# ADC_Test.net
KiCad netlist of a schematic drawn in EAGLE
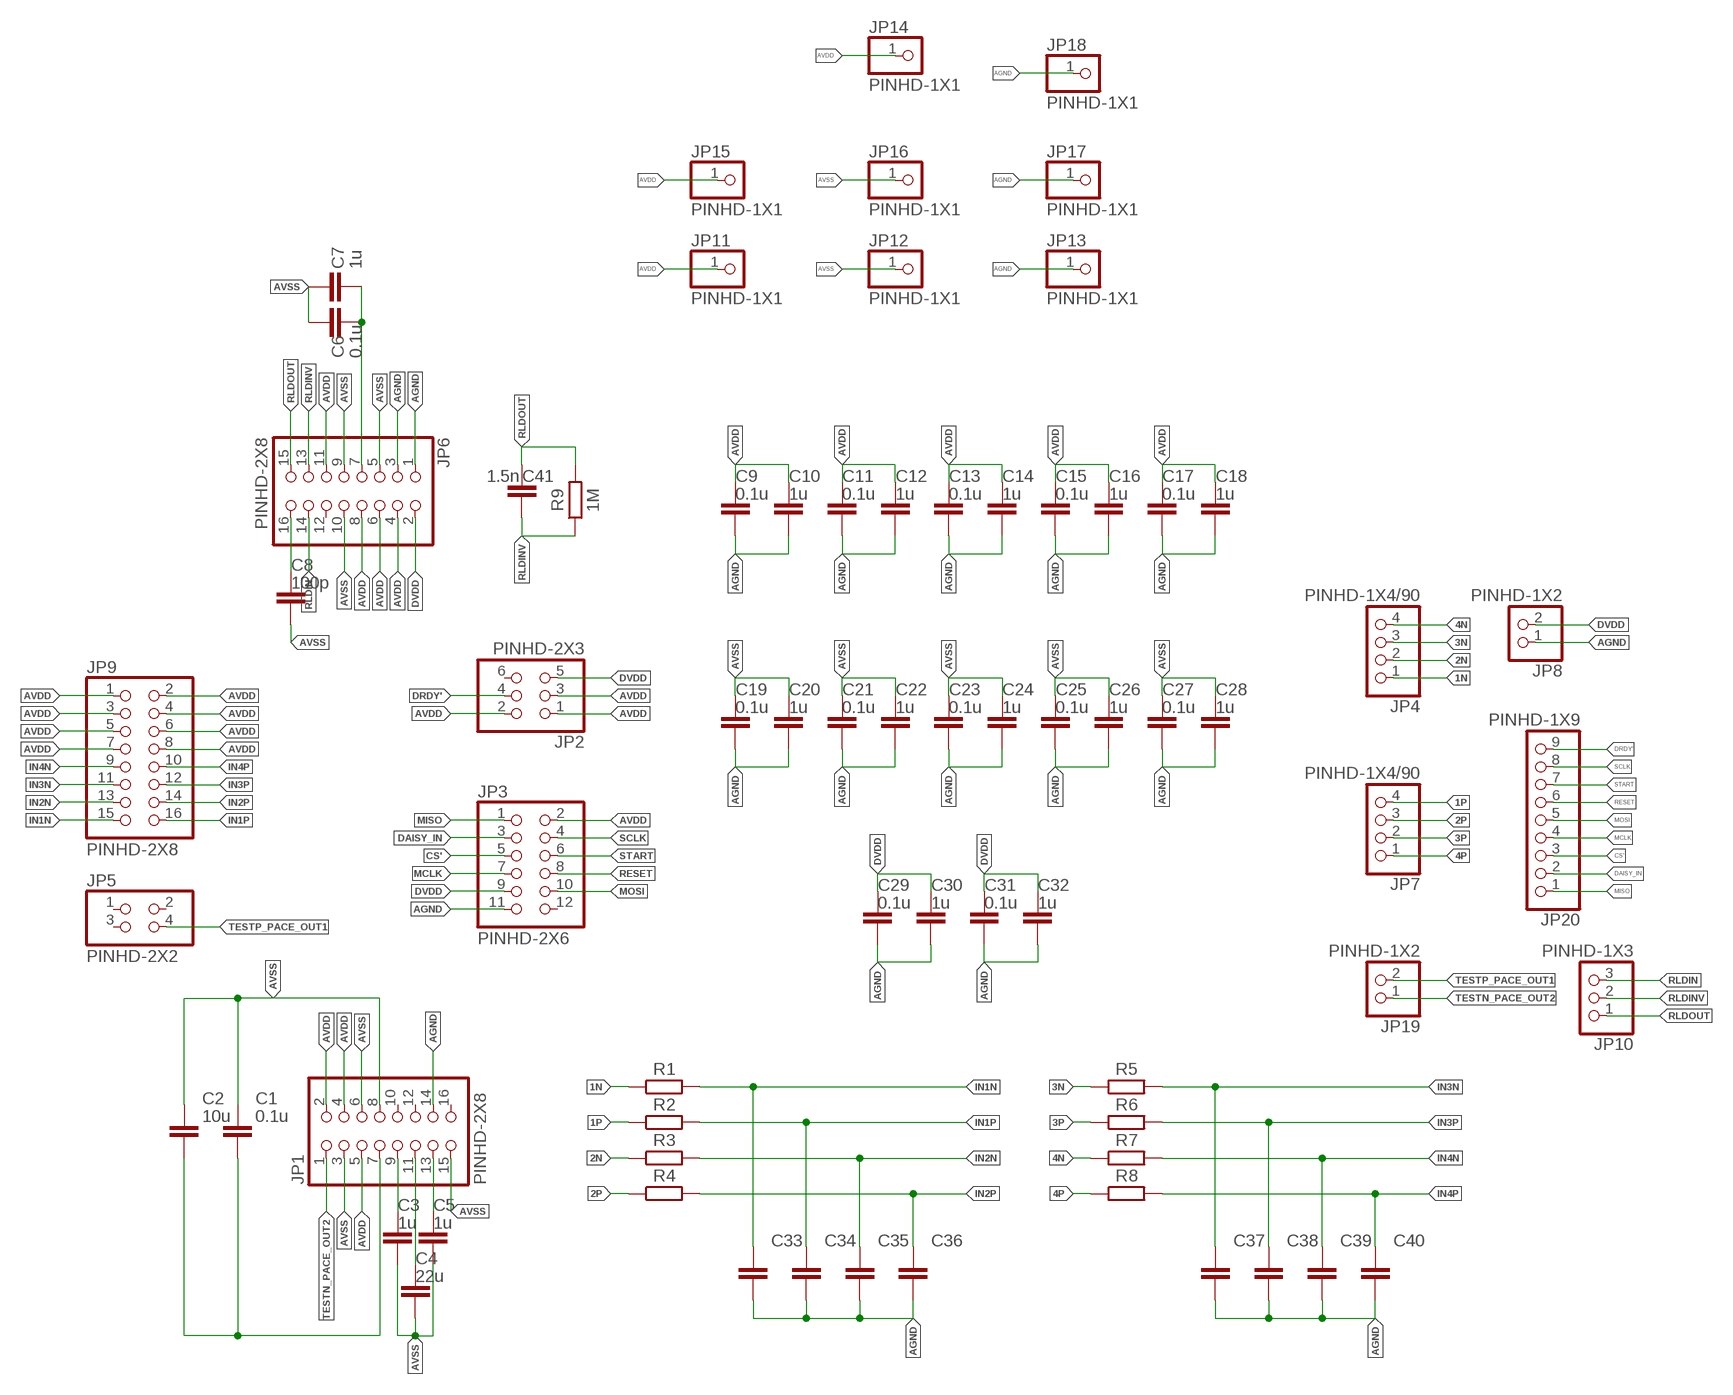
[diagram p0: schematic, sheet 1]

(export (version "E")
  (design (tool "Eeschema 10.0.6"))
  (components
    (comp (ref "C1")
      (value "0.1u")
      (footprint "eagle-import:CAPC2012X110")
      (libsource (lib "eagle-import") (part "CCHIP-0805(2012-METRIC)_"))
    )
    (comp (ref "C2")
      (value "10u")
      (footprint "eagle-import:CAPC2012X110")
      (libsource (lib "eagle-import") (part "CCHIP-0805(2012-METRIC)_"))
    )
    (comp (ref "C3")
      (value "1u")
      (footprint "eagle-import:CAPC2012X110")
      (libsource (lib "eagle-import") (part "CCHIP-0805(2012-METRIC)_"))
    )
    (comp (ref "C4")
      (value "22u")
      (footprint "eagle-import:CAPC2012X110")
      (libsource (lib "eagle-import") (part "CCHIP-0805(2012-METRIC)_"))
    )
    (comp (ref "C5")
      (value "1u")
      (footprint "eagle-import:CAPC2012X110")
      (libsource (lib "eagle-import") (part "CCHIP-0805(2012-METRIC)_"))
    )
    (comp (ref "C6")
      (value "0.1u")
      (footprint "eagle-import:CAPC2012X110")
      (libsource (lib "eagle-import") (part "CCHIP-0805(2012-METRIC)_"))
    )
    (comp (ref "C7")
      (value "1u")
      (footprint "eagle-import:CAPC2012X110")
      (libsource (lib "eagle-import") (part "CCHIP-0805(2012-METRIC)_"))
    )
    (comp (ref "C8")
      (value "100p")
      (footprint "eagle-import:CAPC2012X110")
      (libsource (lib "eagle-import") (part "CCHIP-0805(2012-METRIC)_"))
    )
    (comp (ref "C9")
      (value "0.1u")
      (footprint "eagle-import:CAPC2012X110")
      (libsource (lib "eagle-import") (part "CCHIP-0805(2012-METRIC)_"))
    )
    (comp (ref "C10")
      (value "1u")
      (footprint "eagle-import:CAPC2012X110")
      (libsource (lib "eagle-import") (part "CCHIP-0805(2012-METRIC)_"))
    )
    (comp (ref "C11")
      (value "0.1u")
      (footprint "eagle-import:CAPC2012X110")
      (libsource (lib "eagle-import") (part "CCHIP-0805(2012-METRIC)_"))
    )
    (comp (ref "C12")
      (value "1u")
      (footprint "eagle-import:CAPC2012X110")
      (libsource (lib "eagle-import") (part "CCHIP-0805(2012-METRIC)_"))
    )
    (comp (ref "C13")
      (value "0.1u")
      (footprint "eagle-import:CAPC2012X110")
      (libsource (lib "eagle-import") (part "CCHIP-0805(2012-METRIC)_"))
    )
    (comp (ref "C14")
      (value "1u")
      (footprint "eagle-import:CAPC2012X110")
      (libsource (lib "eagle-import") (part "CCHIP-0805(2012-METRIC)_"))
    )
    (comp (ref "C15")
      (value "0.1u")
      (footprint "eagle-import:CAPC2012X110")
      (libsource (lib "eagle-import") (part "CCHIP-0805(2012-METRIC)_"))
    )
    (comp (ref "C16")
      (value "1u")
      (footprint "eagle-import:CAPC2012X110")
      (libsource (lib "eagle-import") (part "CCHIP-0805(2012-METRIC)_"))
    )
    (comp (ref "C17")
      (value "0.1u")
      (footprint "eagle-import:CAPC2012X110")
      (libsource (lib "eagle-import") (part "CCHIP-0805(2012-METRIC)_"))
    )
    (comp (ref "C18")
      (value "1u")
      (footprint "eagle-import:CAPC2012X110")
      (libsource (lib "eagle-import") (part "CCHIP-0805(2012-METRIC)_"))
    )
    (comp (ref "C19")
      (value "0.1u")
      (footprint "eagle-import:CAPC2012X110")
      (libsource (lib "eagle-import") (part "CCHIP-0805(2012-METRIC)_"))
    )
    (comp (ref "C20")
      (value "1u")
      (footprint "eagle-import:CAPC2012X110")
      (libsource (lib "eagle-import") (part "CCHIP-0805(2012-METRIC)_"))
    )
    (comp (ref "C21")
      (value "0.1u")
      (footprint "eagle-import:CAPC2012X110")
      (libsource (lib "eagle-import") (part "CCHIP-0805(2012-METRIC)_"))
    )
    (comp (ref "C22")
      (value "1u")
      (footprint "eagle-import:CAPC2012X110")
      (libsource (lib "eagle-import") (part "CCHIP-0805(2012-METRIC)_"))
    )
    (comp (ref "C23")
      (value "0.1u")
      (footprint "eagle-import:CAPC2012X110")
      (libsource (lib "eagle-import") (part "CCHIP-0805(2012-METRIC)_"))
    )
    (comp (ref "C24")
      (value "1u")
      (footprint "eagle-import:CAPC2012X110")
      (libsource (lib "eagle-import") (part "CCHIP-0805(2012-METRIC)_"))
    )
    (comp (ref "C25")
      (value "0.1u")
      (footprint "eagle-import:CAPC2012X110")
      (libsource (lib "eagle-import") (part "CCHIP-0805(2012-METRIC)_"))
    )
    (comp (ref "C26")
      (value "1u")
      (footprint "eagle-import:CAPC2012X110")
      (libsource (lib "eagle-import") (part "CCHIP-0805(2012-METRIC)_"))
    )
    (comp (ref "C27")
      (value "0.1u")
      (footprint "eagle-import:CAPC2012X110")
      (libsource (lib "eagle-import") (part "CCHIP-0805(2012-METRIC)_"))
    )
    (comp (ref "C28")
      (value "1u")
      (footprint "eagle-import:CAPC2012X110")
      (libsource (lib "eagle-import") (part "CCHIP-0805(2012-METRIC)_"))
    )
    (comp (ref "C29")
      (value "0.1u")
      (footprint "eagle-import:CAPC2012X110")
      (libsource (lib "eagle-import") (part "CCHIP-0805(2012-METRIC)_"))
    )
    (comp (ref "C30")
      (value "1u")
      (footprint "eagle-import:CAPC2012X110")
      (libsource (lib "eagle-import") (part "CCHIP-0805(2012-METRIC)_"))
    )
    (comp (ref "C31")
      (value "0.1u")
      (footprint "eagle-import:CAPC2012X110")
      (libsource (lib "eagle-import") (part "CCHIP-0805(2012-METRIC)_"))
    )
    (comp (ref "C32")
      (value "1u")
      (footprint "eagle-import:CAPC2012X110")
      (libsource (lib "eagle-import") (part "CCHIP-0805(2012-METRIC)_"))
    )
    (comp (ref "C33")
      (value "C_CHIP-0805(2012-METRIC)")
      (footprint "eagle-import:CAPC2012X110")
      (libsource (lib "eagle-import") (part "CCHIP-0805(2012-METRIC)_"))
    )
    (comp (ref "C34")
      (value "C_CHIP-0805(2012-METRIC)")
      (footprint "eagle-import:CAPC2012X110")
      (libsource (lib "eagle-import") (part "CCHIP-0805(2012-METRIC)_"))
    )
    (comp (ref "C35")
      (value "C_CHIP-0805(2012-METRIC)")
      (footprint "eagle-import:CAPC2012X110")
      (libsource (lib "eagle-import") (part "CCHIP-0805(2012-METRIC)_"))
    )
    (comp (ref "C36")
      (value "C_CHIP-0805(2012-METRIC)")
      (footprint "eagle-import:CAPC2012X110")
      (libsource (lib "eagle-import") (part "CCHIP-0805(2012-METRIC)_"))
    )
    (comp (ref "C37")
      (value "C_CHIP-0805(2012-METRIC)")
      (footprint "eagle-import:CAPC2012X110")
      (libsource (lib "eagle-import") (part "CCHIP-0805(2012-METRIC)_"))
    )
    (comp (ref "C38")
      (value "C_CHIP-0805(2012-METRIC)")
      (footprint "eagle-import:CAPC2012X110")
      (libsource (lib "eagle-import") (part "CCHIP-0805(2012-METRIC)_"))
    )
    (comp (ref "C39")
      (value "C_CHIP-0805(2012-METRIC)")
      (footprint "eagle-import:CAPC2012X110")
      (libsource (lib "eagle-import") (part "CCHIP-0805(2012-METRIC)_"))
    )
    (comp (ref "C40")
      (value "C_CHIP-0805(2012-METRIC)")
      (footprint "eagle-import:CAPC2012X110")
      (libsource (lib "eagle-import") (part "CCHIP-0805(2012-METRIC)_"))
    )
    (comp (ref "C41")
      (value "1.5n")
      (footprint "eagle-import:CAPC2012X110")
      (libsource (lib "eagle-import") (part "CCHIP-0805(2012-METRIC)_"))
    )
    (comp (ref "JP1")
      (value "PINHD-2X8")
      (footprint "eagle-import:2X08")
      (libsource (lib "eagle-import") (part "PINHD-2X8"))
    )
    (comp (ref "JP2")
      (value "PINHD-2X3")
      (footprint "eagle-import:2X03")
      (libsource (lib "eagle-import") (part "PINHD-2X3"))
    )
    (comp (ref "JP3")
      (value "PINHD-2X6")
      (footprint "eagle-import:2X06")
      (libsource (lib "eagle-import") (part "PINHD-2X6"))
    )
    (comp (ref "JP4")
      (value "PINHD-1X4/90")
      (footprint "eagle-import:1X04_90")
      (libsource (lib "eagle-import") (part "PINHD-1X4/90"))
    )
    (comp (ref "JP5")
      (value "PINHD-2X2")
      (footprint "eagle-import:2X02")
      (libsource (lib "eagle-import") (part "PINHD-2X2"))
    )
    (comp (ref "JP6")
      (value "PINHD-2X8")
      (footprint "eagle-import:2X08")
      (libsource (lib "eagle-import") (part "PINHD-2X8"))
    )
    (comp (ref "JP7")
      (value "PINHD-1X4/90")
      (footprint "eagle-import:1X04_90")
      (libsource (lib "eagle-import") (part "PINHD-1X4/90"))
    )
    (comp (ref "JP8")
      (value "PINHD-1X2")
      (footprint "eagle-import:1X02")
      (libsource (lib "eagle-import") (part "PINHD-1X2"))
    )
    (comp (ref "JP9")
      (value "PINHD-2X8")
      (footprint "eagle-import:2X08")
      (libsource (lib "eagle-import") (part "PINHD-2X8"))
    )
    (comp (ref "JP10")
      (value "PINHD-1X3")
      (footprint "eagle-import:1X03")
      (libsource (lib "eagle-import") (part "PINHD-1X3"))
    )
    (comp (ref "JP11")
      (value "PINHD-1X1")
      (footprint "eagle-import:1X01")
      (libsource (lib "eagle-import") (part "PINHD-1X1"))
    )
    (comp (ref "JP12")
      (value "PINHD-1X1")
      (footprint "eagle-import:1X01")
      (libsource (lib "eagle-import") (part "PINHD-1X1"))
    )
    (comp (ref "JP13")
      (value "PINHD-1X1")
      (footprint "eagle-import:1X01")
      (libsource (lib "eagle-import") (part "PINHD-1X1"))
    )
    (comp (ref "JP14")
      (value "PINHD-1X1")
      (footprint "eagle-import:1X01")
      (libsource (lib "eagle-import") (part "PINHD-1X1"))
    )
    (comp (ref "JP15")
      (value "PINHD-1X1")
      (footprint "eagle-import:1X01")
      (libsource (lib "eagle-import") (part "PINHD-1X1"))
    )
    (comp (ref "JP16")
      (value "PINHD-1X1")
      (footprint "eagle-import:1X01")
      (libsource (lib "eagle-import") (part "PINHD-1X1"))
    )
    (comp (ref "JP17")
      (value "PINHD-1X1")
      (footprint "eagle-import:1X01")
      (libsource (lib "eagle-import") (part "PINHD-1X1"))
    )
    (comp (ref "JP18")
      (value "PINHD-1X1")
      (footprint "eagle-import:1X01")
      (libsource (lib "eagle-import") (part "PINHD-1X1"))
    )
    (comp (ref "JP19")
      (value "PINHD-1X2")
      (footprint "eagle-import:1X02")
      (libsource (lib "eagle-import") (part "PINHD-1X2"))
    )
    (comp (ref "JP20")
      (value "PINHD-1X9")
      (footprint "eagle-import:1X09")
      (libsource (lib "eagle-import") (part "PINHD-1X9"))
    )
    (comp (ref "R1")
      (value "R_CHIP-1206(3216-METRIC)")
      (footprint "eagle-import:RESC3216X70")
      (libsource (lib "eagle-import") (part "RCHIP-1206(3216-METRIC)_"))
    )
    (comp (ref "R2")
      (value "R_CHIP-1206(3216-METRIC)")
      (footprint "eagle-import:RESC3216X70")
      (libsource (lib "eagle-import") (part "RCHIP-1206(3216-METRIC)_"))
    )
    (comp (ref "R3")
      (value "R_CHIP-1206(3216-METRIC)")
      (footprint "eagle-import:RESC3216X70")
      (libsource (lib "eagle-import") (part "RCHIP-1206(3216-METRIC)_"))
    )
    (comp (ref "R4")
      (value "R_CHIP-1206(3216-METRIC)")
      (footprint "eagle-import:RESC3216X70")
      (libsource (lib "eagle-import") (part "RCHIP-1206(3216-METRIC)_"))
    )
    (comp (ref "R5")
      (value "R_CHIP-1206(3216-METRIC)")
      (footprint "eagle-import:RESC3216X70")
      (libsource (lib "eagle-import") (part "RCHIP-1206(3216-METRIC)_"))
    )
    (comp (ref "R6")
      (value "R_CHIP-1206(3216-METRIC)")
      (footprint "eagle-import:RESC3216X70")
      (libsource (lib "eagle-import") (part "RCHIP-1206(3216-METRIC)_"))
    )
    (comp (ref "R7")
      (value "R_CHIP-1206(3216-METRIC)")
      (footprint "eagle-import:RESC3216X70")
      (libsource (lib "eagle-import") (part "RCHIP-1206(3216-METRIC)_"))
    )
    (comp (ref "R8")
      (value "R_CHIP-1206(3216-METRIC)")
      (footprint "eagle-import:RESC3216X70")
      (libsource (lib "eagle-import") (part "RCHIP-1206(3216-METRIC)_"))
    )
    (comp (ref "R9")
      (value "1M")
      (footprint "eagle-import:RESC3216X70")
      (libsource (lib "eagle-import") (part "RCHIP-1206(3216-METRIC)_"))
    )
  )
  (nets
    (net (code "1") (name "1N") (class "Default")
      (node (ref "JP4") (pin "1") (pinfunction "1_1") (pintype "passive"))
      (node (ref "R1") (pin "1") (pinfunction "1_1") (pintype "passive"))
    )
    (net (code "2") (name "1P") (class "Default")
      (node (ref "JP7") (pin "4") (pinfunction "4_4") (pintype "passive"))
      (node (ref "R2") (pin "1") (pinfunction "1_1") (pintype "passive"))
    )
    (net (code "3") (name "2N") (class "Default")
      (node (ref "JP4") (pin "2") (pinfunction "2_2") (pintype "passive"))
      (node (ref "R3") (pin "1") (pinfunction "1_1") (pintype "passive"))
    )
    (net (code "4") (name "2P") (class "Default")
      (node (ref "JP7") (pin "3") (pinfunction "3_3") (pintype "passive"))
      (node (ref "R4") (pin "1") (pinfunction "1_1") (pintype "passive"))
    )
    (net (code "5") (name "3N") (class "Default")
      (node (ref "JP4") (pin "3") (pinfunction "3_3") (pintype "passive"))
      (node (ref "R5") (pin "1") (pinfunction "1_1") (pintype "passive"))
    )
    (net (code "6") (name "3P") (class "Default")
      (node (ref "JP7") (pin "2") (pinfunction "2_2") (pintype "passive"))
      (node (ref "R6") (pin "1") (pinfunction "1_1") (pintype "passive"))
    )
    (net (code "7") (name "4N") (class "Default")
      (node (ref "JP4") (pin "4") (pinfunction "4_4") (pintype "passive"))
      (node (ref "R7") (pin "1") (pinfunction "1_1") (pintype "passive"))
    )
    (net (code "8") (name "4P") (class "Default")
      (node (ref "JP7") (pin "1") (pinfunction "1_1") (pintype "passive"))
      (node (ref "R8") (pin "1") (pinfunction "1_1") (pintype "passive"))
    )
    (net (code "9") (name "AGND") (class "Default")
      (node (ref "C10") (pin "2") (pinfunction "2_2") (pintype "passive"))
      (node (ref "C11") (pin "2") (pinfunction "2_2") (pintype "passive"))
      (node (ref "C12") (pin "2") (pinfunction "2_2") (pintype "passive"))
      (node (ref "C13") (pin "2") (pinfunction "2_2") (pintype "passive"))
      (node (ref "C14") (pin "2") (pinfunction "2_2") (pintype "passive"))
      (node (ref "C15") (pin "2") (pinfunction "2_2") (pintype "passive"))
      (node (ref "C16") (pin "2") (pinfunction "2_2") (pintype "passive"))
      (node (ref "C17") (pin "2") (pinfunction "2_2") (pintype "passive"))
      (node (ref "C18") (pin "2") (pinfunction "2_2") (pintype "passive"))
      (node (ref "C19") (pin "2") (pinfunction "2_2") (pintype "passive"))
      (node (ref "C20") (pin "2") (pinfunction "2_2") (pintype "passive"))
      (node (ref "C21") (pin "2") (pinfunction "2_2") (pintype "passive"))
      (node (ref "C22") (pin "2") (pinfunction "2_2") (pintype "passive"))
      (node (ref "C23") (pin "2") (pinfunction "2_2") (pintype "passive"))
      (node (ref "C24") (pin "2") (pinfunction "2_2") (pintype "passive"))
      (node (ref "C25") (pin "2") (pinfunction "2_2") (pintype "passive"))
      (node (ref "C26") (pin "2") (pinfunction "2_2") (pintype "passive"))
      (node (ref "C27") (pin "2") (pinfunction "2_2") (pintype "passive"))
      (node (ref "C28") (pin "2") (pinfunction "2_2") (pintype "passive"))
      (node (ref "C29") (pin "2") (pinfunction "2_2") (pintype "passive"))
      (node (ref "C30") (pin "2") (pinfunction "2_2") (pintype "passive"))
      (node (ref "C31") (pin "2") (pinfunction "2_2") (pintype "passive"))
      (node (ref "C32") (pin "2") (pinfunction "2_2") (pintype "passive"))
      (node (ref "C33") (pin "2") (pinfunction "2_2") (pintype "passive"))
      (node (ref "C34") (pin "2") (pinfunction "2_2") (pintype "passive"))
      (node (ref "C35") (pin "2") (pinfunction "2_2") (pintype "passive"))
      (node (ref "C36") (pin "2") (pinfunction "2_2") (pintype "passive"))
      (node (ref "C37") (pin "2") (pinfunction "2_2") (pintype "passive"))
      (node (ref "C38") (pin "2") (pinfunction "2_2") (pintype "passive"))
      (node (ref "C39") (pin "2") (pinfunction "2_2") (pintype "passive"))
      (node (ref "C40") (pin "2") (pinfunction "2_2") (pintype "passive"))
      (node (ref "C9") (pin "2") (pinfunction "2_2") (pintype "passive"))
      (node (ref "JP1") (pin "14") (pinfunction "14_14") (pintype "passive"))
      (node (ref "JP13") (pin "1") (pinfunction "1_1") (pintype "passive"))
      (node (ref "JP17") (pin "1") (pinfunction "1_1") (pintype "passive"))
      (node (ref "JP18") (pin "1") (pinfunction "1_1") (pintype "passive"))
      (node (ref "JP3") (pin "11") (pinfunction "11_11") (pintype "passive"))
      (node (ref "JP6") (pin "1") (pinfunction "1_1") (pintype "passive"))
      (node (ref "JP6") (pin "3") (pinfunction "3_3") (pintype "passive"))
      (node (ref "JP8") (pin "1") (pinfunction "1_1") (pintype "passive"))
    )
    (net (code "10") (name "AVDD") (class "Default")
      (node (ref "C10") (pin "1") (pinfunction "1_1") (pintype "passive"))
      (node (ref "C11") (pin "1") (pinfunction "1_1") (pintype "passive"))
      (node (ref "C12") (pin "1") (pinfunction "1_1") (pintype "passive"))
      (node (ref "C13") (pin "1") (pinfunction "1_1") (pintype "passive"))
      (node (ref "C14") (pin "1") (pinfunction "1_1") (pintype "passive"))
      (node (ref "C15") (pin "1") (pinfunction "1_1") (pintype "passive"))
      (node (ref "C16") (pin "1") (pinfunction "1_1") (pintype "passive"))
      (node (ref "C17") (pin "1") (pinfunction "1_1") (pintype "passive"))
      (node (ref "C18") (pin "1") (pinfunction "1_1") (pintype "passive"))
      (node (ref "C9") (pin "1") (pinfunction "1_1") (pintype "passive"))
      (node (ref "JP1") (pin "2") (pinfunction "2_2") (pintype "passive"))
      (node (ref "JP1") (pin "4") (pinfunction "4_4") (pintype "passive"))
      (node (ref "JP1") (pin "5") (pinfunction "5_5") (pintype "passive"))
      (node (ref "JP11") (pin "1") (pinfunction "1_1") (pintype "passive"))
      (node (ref "JP14") (pin "1") (pinfunction "1_1") (pintype "passive"))
      (node (ref "JP15") (pin "1") (pinfunction "1_1") (pintype "passive"))
      (node (ref "JP2") (pin "1") (pinfunction "1_1") (pintype "passive"))
      (node (ref "JP2") (pin "2") (pinfunction "2_2") (pintype "passive"))
      (node (ref "JP2") (pin "3") (pinfunction "3_3") (pintype "passive"))
      (node (ref "JP3") (pin "2") (pinfunction "2_2") (pintype "passive"))
      (node (ref "JP6") (pin "11") (pinfunction "11_11") (pintype "passive"))
      (node (ref "JP6") (pin "4") (pinfunction "4_4") (pintype "passive"))
      (node (ref "JP6") (pin "6") (pinfunction "6_6") (pintype "passive"))
      (node (ref "JP6") (pin "8") (pinfunction "8_8") (pintype "passive"))
      (node (ref "JP9") (pin "1") (pinfunction "1_1") (pintype "passive"))
      (node (ref "JP9") (pin "2") (pinfunction "2_2") (pintype "passive"))
      (node (ref "JP9") (pin "3") (pinfunction "3_3") (pintype "passive"))
      (node (ref "JP9") (pin "4") (pinfunction "4_4") (pintype "passive"))
      (node (ref "JP9") (pin "5") (pinfunction "5_5") (pintype "passive"))
      (node (ref "JP9") (pin "6") (pinfunction "6_6") (pintype "passive"))
      (node (ref "JP9") (pin "7") (pinfunction "7_7") (pintype "passive"))
      (node (ref "JP9") (pin "8") (pinfunction "8_8") (pintype "passive"))
    )
    (net (code "11") (name "AVSS") (class "Default")
      (node (ref "C1") (pin "1") (pinfunction "1_1") (pintype "passive"))
      (node (ref "C19") (pin "1") (pinfunction "1_1") (pintype "passive"))
      (node (ref "C2") (pin "1") (pinfunction "1_1") (pintype "passive"))
      (node (ref "C20") (pin "1") (pinfunction "1_1") (pintype "passive"))
      (node (ref "C21") (pin "1") (pinfunction "1_1") (pintype "passive"))
      (node (ref "C22") (pin "1") (pinfunction "1_1") (pintype "passive"))
      (node (ref "C23") (pin "1") (pinfunction "1_1") (pintype "passive"))
      (node (ref "C24") (pin "1") (pinfunction "1_1") (pintype "passive"))
      (node (ref "C25") (pin "1") (pinfunction "1_1") (pintype "passive"))
      (node (ref "C26") (pin "1") (pinfunction "1_1") (pintype "passive"))
      (node (ref "C27") (pin "1") (pinfunction "1_1") (pintype "passive"))
      (node (ref "C28") (pin "1") (pinfunction "1_1") (pintype "passive"))
      (node (ref "C3") (pin "2") (pinfunction "2_2") (pintype "passive"))
      (node (ref "C4") (pin "2") (pinfunction "2_2") (pintype "passive"))
      (node (ref "C5") (pin "2") (pinfunction "2_2") (pintype "passive"))
      (node (ref "C6") (pin "1") (pinfunction "1_1") (pintype "passive"))
      (node (ref "C7") (pin "1") (pinfunction "1_1") (pintype "passive"))
      (node (ref "C8") (pin "2") (pinfunction "2_2") (pintype "passive"))
      (node (ref "JP1") (pin "15") (pinfunction "15_15") (pintype "passive"))
      (node (ref "JP1") (pin "3") (pinfunction "3_3") (pintype "passive"))
      (node (ref "JP1") (pin "6") (pinfunction "6_6") (pintype "passive"))
      (node (ref "JP1") (pin "8") (pinfunction "8_8") (pintype "passive"))
      (node (ref "JP12") (pin "1") (pinfunction "1_1") (pintype "passive"))
      (node (ref "JP16") (pin "1") (pinfunction "1_1") (pintype "passive"))
      (node (ref "JP6") (pin "10") (pinfunction "10_10") (pintype "passive"))
      (node (ref "JP6") (pin "5") (pinfunction "5_5") (pintype "passive"))
      (node (ref "JP6") (pin "9") (pinfunction "9_9") (pintype "passive"))
    )
    (net (code "12") (name "CS'") (class "Default")
      (node (ref "JP20") (pin "3") (pinfunction "3_3") (pintype "passive"))
      (node (ref "JP3") (pin "5") (pinfunction "5_5") (pintype "passive"))
    )
    (net (code "13") (name "DAISY_IN") (class "Default")
      (node (ref "JP20") (pin "2") (pinfunction "2_2") (pintype "passive"))
      (node (ref "JP3") (pin "3") (pinfunction "3_3") (pintype "passive"))
    )
    (net (code "14") (name "DRDY'") (class "Default")
      (node (ref "JP2") (pin "4") (pinfunction "4_4") (pintype "passive"))
      (node (ref "JP20") (pin "9") (pinfunction "9_9") (pintype "passive"))
    )
    (net (code "15") (name "DVDD") (class "Default")
      (node (ref "C29") (pin "1") (pinfunction "1_1") (pintype "passive"))
      (node (ref "C30") (pin "1") (pinfunction "1_1") (pintype "passive"))
      (node (ref "C31") (pin "1") (pinfunction "1_1") (pintype "passive"))
      (node (ref "C32") (pin "1") (pinfunction "1_1") (pintype "passive"))
      (node (ref "JP2") (pin "5") (pinfunction "5_5") (pintype "passive"))
      (node (ref "JP3") (pin "9") (pinfunction "9_9") (pintype "passive"))
      (node (ref "JP6") (pin "2") (pinfunction "2_2") (pintype "passive"))
      (node (ref "JP8") (pin "2") (pinfunction "2_2") (pintype "passive"))
    )
    (net (code "16") (name "IN1N") (class "Default")
      (node (ref "C33") (pin "1") (pinfunction "1_1") (pintype "passive"))
      (node (ref "JP9") (pin "15") (pinfunction "15_15") (pintype "passive"))
      (node (ref "R1") (pin "2") (pinfunction "2_2") (pintype "passive"))
    )
    (net (code "17") (name "IN1P") (class "Default")
      (node (ref "C34") (pin "1") (pinfunction "1_1") (pintype "passive"))
      (node (ref "JP9") (pin "16") (pinfunction "16_16") (pintype "passive"))
      (node (ref "R2") (pin "2") (pinfunction "2_2") (pintype "passive"))
    )
    (net (code "18") (name "IN2N") (class "Default")
      (node (ref "C35") (pin "1") (pinfunction "1_1") (pintype "passive"))
      (node (ref "JP9") (pin "13") (pinfunction "13_13") (pintype "passive"))
      (node (ref "R3") (pin "2") (pinfunction "2_2") (pintype "passive"))
    )
    (net (code "19") (name "IN2P") (class "Default")
      (node (ref "C36") (pin "1") (pinfunction "1_1") (pintype "passive"))
      (node (ref "JP9") (pin "14") (pinfunction "14_14") (pintype "passive"))
      (node (ref "R4") (pin "2") (pinfunction "2_2") (pintype "passive"))
    )
    (net (code "20") (name "IN3N") (class "Default")
      (node (ref "C37") (pin "1") (pinfunction "1_1") (pintype "passive"))
      (node (ref "JP9") (pin "11") (pinfunction "11_11") (pintype "passive"))
      (node (ref "R5") (pin "2") (pinfunction "2_2") (pintype "passive"))
    )
    (net (code "21") (name "IN3P") (class "Default")
      (node (ref "C38") (pin "1") (pinfunction "1_1") (pintype "passive"))
      (node (ref "JP9") (pin "12") (pinfunction "12_12") (pintype "passive"))
      (node (ref "R6") (pin "2") (pinfunction "2_2") (pintype "passive"))
    )
    (net (code "22") (name "IN4N") (class "Default")
      (node (ref "C39") (pin "1") (pinfunction "1_1") (pintype "passive"))
      (node (ref "JP9") (pin "9") (pinfunction "9_9") (pintype "passive"))
      (node (ref "R7") (pin "2") (pinfunction "2_2") (pintype "passive"))
    )
    (net (code "23") (name "IN4P") (class "Default")
      (node (ref "C40") (pin "1") (pinfunction "1_1") (pintype "passive"))
      (node (ref "JP9") (pin "10") (pinfunction "10_10") (pintype "passive"))
      (node (ref "R8") (pin "2") (pinfunction "2_2") (pintype "passive"))
    )
    (net (code "24") (name "MCLK") (class "Default")
      (node (ref "JP20") (pin "4") (pinfunction "4_4") (pintype "passive"))
      (node (ref "JP3") (pin "7") (pinfunction "7_7") (pintype "passive"))
    )
    (net (code "25") (name "MISO") (class "Default")
      (node (ref "JP20") (pin "1") (pinfunction "1_1") (pintype "passive"))
      (node (ref "JP3") (pin "1") (pinfunction "1_1") (pintype "passive"))
    )
    (net (code "26") (name "MOSI") (class "Default")
      (node (ref "JP20") (pin "5") (pinfunction "5_5") (pintype "passive"))
      (node (ref "JP3") (pin "10") (pinfunction "10_10") (pintype "passive"))
    )
    (net (code "27") (name "Net-(C1-Pad2)") (class "Default")
      (node (ref "C1") (pin "2") (pinfunction "2_2") (pintype "passive"))
      (node (ref "C2") (pin "2") (pinfunction "2_2") (pintype "passive"))
      (node (ref "JP1") (pin "7") (pinfunction "7_7") (pintype "passive"))
    )
    (net (code "28") (name "Net-(C3-Pad1)") (class "Default")
      (node (ref "C3") (pin "1") (pinfunction "1_1") (pintype "passive"))
      (node (ref "JP1") (pin "9") (pinfunction "9_9") (pintype "passive"))
    )
    (net (code "29") (name "Net-(C4-Pad1)") (class "Default")
      (node (ref "C4") (pin "1") (pinfunction "1_1") (pintype "passive"))
      (node (ref "JP1") (pin "11") (pinfunction "11_11") (pintype "passive"))
    )
    (net (code "30") (name "Net-(C5-Pad1)") (class "Default")
      (node (ref "C5") (pin "1") (pinfunction "1_1") (pintype "passive"))
      (node (ref "JP1") (pin "13") (pinfunction "13_13") (pintype "passive"))
    )
    (net (code "31") (name "Net-(C6-Pad2)") (class "Default")
      (node (ref "C6") (pin "2") (pinfunction "2_2") (pintype "passive"))
      (node (ref "C7") (pin "2") (pinfunction "2_2") (pintype "passive"))
      (node (ref "JP6") (pin "7") (pinfunction "7_7") (pintype "passive"))
    )
    (net (code "32") (name "Net-(C8-Pad1)") (class "Default")
      (node (ref "C8") (pin "1") (pinfunction "1_1") (pintype "passive"))
      (node (ref "JP6") (pin "16") (pinfunction "16_16") (pintype "passive"))
    )
    (net (code "33") (name "RESET") (class "Default")
      (node (ref "JP20") (pin "6") (pinfunction "6_6") (pintype "passive"))
      (node (ref "JP3") (pin "8") (pinfunction "8_8") (pintype "passive"))
    )
    (net (code "34") (name "RLDIN") (class "Default")
      (node (ref "JP10") (pin "3") (pinfunction "3_3") (pintype "passive"))
      (node (ref "JP6") (pin "14") (pinfunction "14_14") (pintype "passive"))
    )
    (net (code "35") (name "RLDINV") (class "Default")
      (node (ref "C41") (pin "2") (pinfunction "2_2") (pintype "passive"))
      (node (ref "JP10") (pin "2") (pinfunction "2_2") (pintype "passive"))
      (node (ref "JP6") (pin "13") (pinfunction "13_13") (pintype "passive"))
      (node (ref "R9") (pin "1") (pinfunction "1_1") (pintype "passive"))
    )
    (net (code "36") (name "RLDOUT") (class "Default")
      (node (ref "C41") (pin "1") (pinfunction "1_1") (pintype "passive"))
      (node (ref "JP10") (pin "1") (pinfunction "1_1") (pintype "passive"))
      (node (ref "JP6") (pin "15") (pinfunction "15_15") (pintype "passive"))
      (node (ref "R9") (pin "2") (pinfunction "2_2") (pintype "passive"))
    )
    (net (code "37") (name "SCLK") (class "Default")
      (node (ref "JP20") (pin "8") (pinfunction "8_8") (pintype "passive"))
      (node (ref "JP3") (pin "4") (pinfunction "4_4") (pintype "passive"))
    )
    (net (code "38") (name "START") (class "Default")
      (node (ref "JP20") (pin "7") (pinfunction "7_7") (pintype "passive"))
      (node (ref "JP3") (pin "6") (pinfunction "6_6") (pintype "passive"))
    )
    (net (code "39") (name "TESTN_PACE_OUT2") (class "Default")
      (node (ref "JP1") (pin "1") (pinfunction "1_1") (pintype "passive"))
      (node (ref "JP19") (pin "1") (pinfunction "1_1") (pintype "passive"))
    )
    (net (code "40") (name "TESTP_PACE_OUT1") (class "Default")
      (node (ref "JP19") (pin "2") (pinfunction "2_2") (pintype "passive"))
      (node (ref "JP5") (pin "4") (pinfunction "4_4") (pintype "passive"))
    )
    (net (code "41") (name "unconnected-(JP1-Pad10)") (class "Default")
      (node (ref "JP1") (pin "10") (pinfunction "10_10") (pintype "passive"))
    )
    (net (code "42") (name "unconnected-(JP1-Pad12)") (class "Default")
      (node (ref "JP1") (pin "12") (pinfunction "12_12") (pintype "passive"))
    )
    (net (code "43") (name "unconnected-(JP1-Pad16)") (class "Default")
      (node (ref "JP1") (pin "16") (pinfunction "16_16") (pintype "passive"))
    )
    (net (code "44") (name "unconnected-(JP2-Pad6)") (class "Default")
      (node (ref "JP2") (pin "6") (pinfunction "6_6") (pintype "passive"))
    )
    (net (code "45") (name "unconnected-(JP3-Pad12)") (class "Default")
      (node (ref "JP3") (pin "12") (pinfunction "12_12") (pintype "passive"))
    )
    (net (code "46") (name "unconnected-(JP5-Pad1)") (class "Default")
      (node (ref "JP5") (pin "1") (pinfunction "1_1") (pintype "passive"))
    )
    (net (code "47") (name "unconnected-(JP5-Pad2)") (class "Default")
      (node (ref "JP5") (pin "2") (pinfunction "2_2") (pintype "passive"))
    )
    (net (code "48") (name "unconnected-(JP5-Pad3)") (class "Default")
      (node (ref "JP5") (pin "3") (pinfunction "3_3") (pintype "passive"))
    )
    (net (code "49") (name "unconnected-(JP6-Pad12)") (class "Default")
      (node (ref "JP6") (pin "12") (pinfunction "12_12") (pintype "passive"))
    )
  )
)
